# M_M_ext_meteo_RJ11.net
KiCad netlist of a schematic drawn in EAGLE
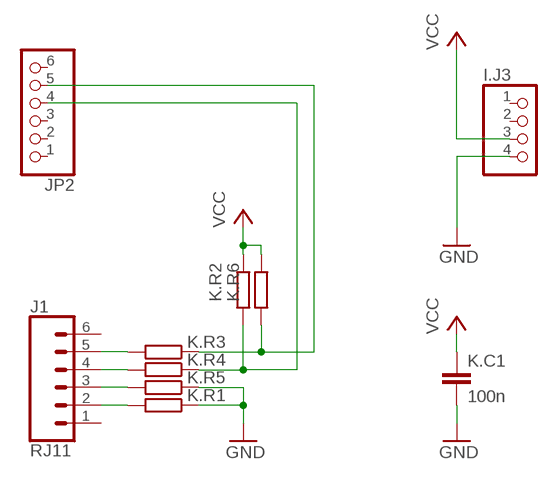
[diagram p0: schematic, sheet 1]

(export (version "E")
  (design (tool "Eeschema 10.0.6"))
  (components
    (comp (ref "I.J3")
      (value "PINHD-1X4")
      (footprint "eagle-import:1X04")
      (libsource (lib "eagle-import") (part "PINHD-1X4"))
    )
    (comp (ref "J1")
      (value "RJ11")
      (footprint "eagle-import:RJ11-6")
      (libsource (lib "eagle-import") (part "RJ11-6"))
    )
    (comp (ref "JP2")
      (value "PINHD-1X6")
      (footprint "eagle-import:1X06")
      (libsource (lib "eagle-import") (part "PINHD-1X6"))
    )
    (comp (ref "K.C1")
      (value "100n")
      (footprint "eagle-import:C0603")
      (libsource (lib "eagle-import") (part "C-EUC0603"))
    )
    (comp (ref "K.R1")
      (value "100")
      (footprint "eagle-import:R0603")
      (libsource (lib "eagle-import") (part "R-EU_R0603"))
    )
    (comp (ref "K.R2")
      (value "10k")
      (footprint "eagle-import:R0603")
      (libsource (lib "eagle-import") (part "R-EU_R0603"))
    )
    (comp (ref "K.R3")
      (value "100")
      (footprint "eagle-import:R0603")
      (libsource (lib "eagle-import") (part "R-EU_R0603"))
    )
    (comp (ref "K.R4")
      (value "100")
      (footprint "eagle-import:R0603")
      (libsource (lib "eagle-import") (part "R-EU_R0603"))
    )
    (comp (ref "K.R5")
      (value "100")
      (footprint "eagle-import:R0603")
      (libsource (lib "eagle-import") (part "R-EU_R0603"))
    )
    (comp (ref "K.R6")
      (value "10k")
      (footprint "eagle-import:R0603")
      (libsource (lib "eagle-import") (part "R-EU_R0603"))
    )
  )
  (nets
    (net (code "1") (name "GND") (class "Default")
      (node (ref "I.J3") (pin "4") (pinfunction "4_4") (pintype "passive"))
      (node (ref "K.C1") (pin "2") (pinfunction "2_2") (pintype "passive"))
      (node (ref "K.R1") (pin "1") (pinfunction "1_1") (pintype "passive"))
      (node (ref "K.R5") (pin "1") (pinfunction "1_1") (pintype "passive"))
    )
    (net (code "2") (name "Net-(J1-Pad2)") (class "Default")
      (node (ref "J1") (pin "2") (pinfunction "2_2") (pintype "passive"))
      (node (ref "K.R1") (pin "2") (pinfunction "2_2") (pintype "passive"))
    )
    (net (code "3") (name "Net-(J1-Pad3)") (class "Default")
      (node (ref "J1") (pin "3") (pinfunction "3_3") (pintype "passive"))
      (node (ref "K.R5") (pin "2") (pinfunction "2_2") (pintype "passive"))
    )
    (net (code "4") (name "Net-(J1-Pad4)") (class "Default")
      (node (ref "J1") (pin "4") (pinfunction "4_4") (pintype "passive"))
      (node (ref "K.R4") (pin "2") (pinfunction "2_2") (pintype "passive"))
    )
    (net (code "5") (name "Net-(J1-Pad5)") (class "Default")
      (node (ref "J1") (pin "5") (pinfunction "5_5") (pintype "passive"))
      (node (ref "K.R3") (pin "2") (pinfunction "2_2") (pintype "passive"))
    )
    (net (code "6") (name "Net-(JP2-Pad4)") (class "Default")
      (node (ref "JP2") (pin "4") (pinfunction "4_4") (pintype "passive"))
      (node (ref "K.R2") (pin "2") (pinfunction "2_2") (pintype "passive"))
      (node (ref "K.R4") (pin "1") (pinfunction "1_1") (pintype "passive"))
    )
    (net (code "7") (name "Net-(JP2-Pad5)") (class "Default")
      (node (ref "JP2") (pin "5") (pinfunction "5_5") (pintype "passive"))
      (node (ref "K.R3") (pin "1") (pinfunction "1_1") (pintype "passive"))
      (node (ref "K.R6") (pin "2") (pinfunction "2_2") (pintype "passive"))
    )
    (net (code "8") (name "VCC") (class "Default")
      (node (ref "I.J3") (pin "3") (pinfunction "3_3") (pintype "passive"))
      (node (ref "K.C1") (pin "1") (pinfunction "1_1") (pintype "passive"))
      (node (ref "K.R2") (pin "1") (pinfunction "1_1") (pintype "passive"))
      (node (ref "K.R6") (pin "1") (pinfunction "1_1") (pintype "passive"))
    )
    (net (code "9") (name "unconnected-(I.J3-Pad1)") (class "Default")
      (node (ref "I.J3") (pin "1") (pinfunction "1_1") (pintype "passive"))
    )
    (net (code "10") (name "unconnected-(I.J3-Pad2)") (class "Default")
      (node (ref "I.J3") (pin "2") (pinfunction "2_2") (pintype "passive"))
    )
    (net (code "11") (name "unconnected-(J1-Pad1)") (class "Default")
      (node (ref "J1") (pin "1") (pinfunction "1_1") (pintype "passive"))
    )
    (net (code "12") (name "unconnected-(J1-Pad6)") (class "Default")
      (node (ref "J1") (pin "6") (pinfunction "6_6") (pintype "passive"))
    )
    (net (code "13") (name "unconnected-(JP2-Pad1)") (class "Default")
      (node (ref "JP2") (pin "1") (pinfunction "1_1") (pintype "passive"))
    )
    (net (code "14") (name "unconnected-(JP2-Pad2)") (class "Default")
      (node (ref "JP2") (pin "2") (pinfunction "2_2") (pintype "passive"))
    )
    (net (code "15") (name "unconnected-(JP2-Pad3)") (class "Default")
      (node (ref "JP2") (pin "3") (pinfunction "3_3") (pintype "passive"))
    )
    (net (code "16") (name "unconnected-(JP2-Pad6)") (class "Default")
      (node (ref "JP2") (pin "6") (pinfunction "6_6") (pintype "passive"))
    )
  )
)
